# Robot_Psoc.net
KiCad netlist of a schematic drawn in EAGLE
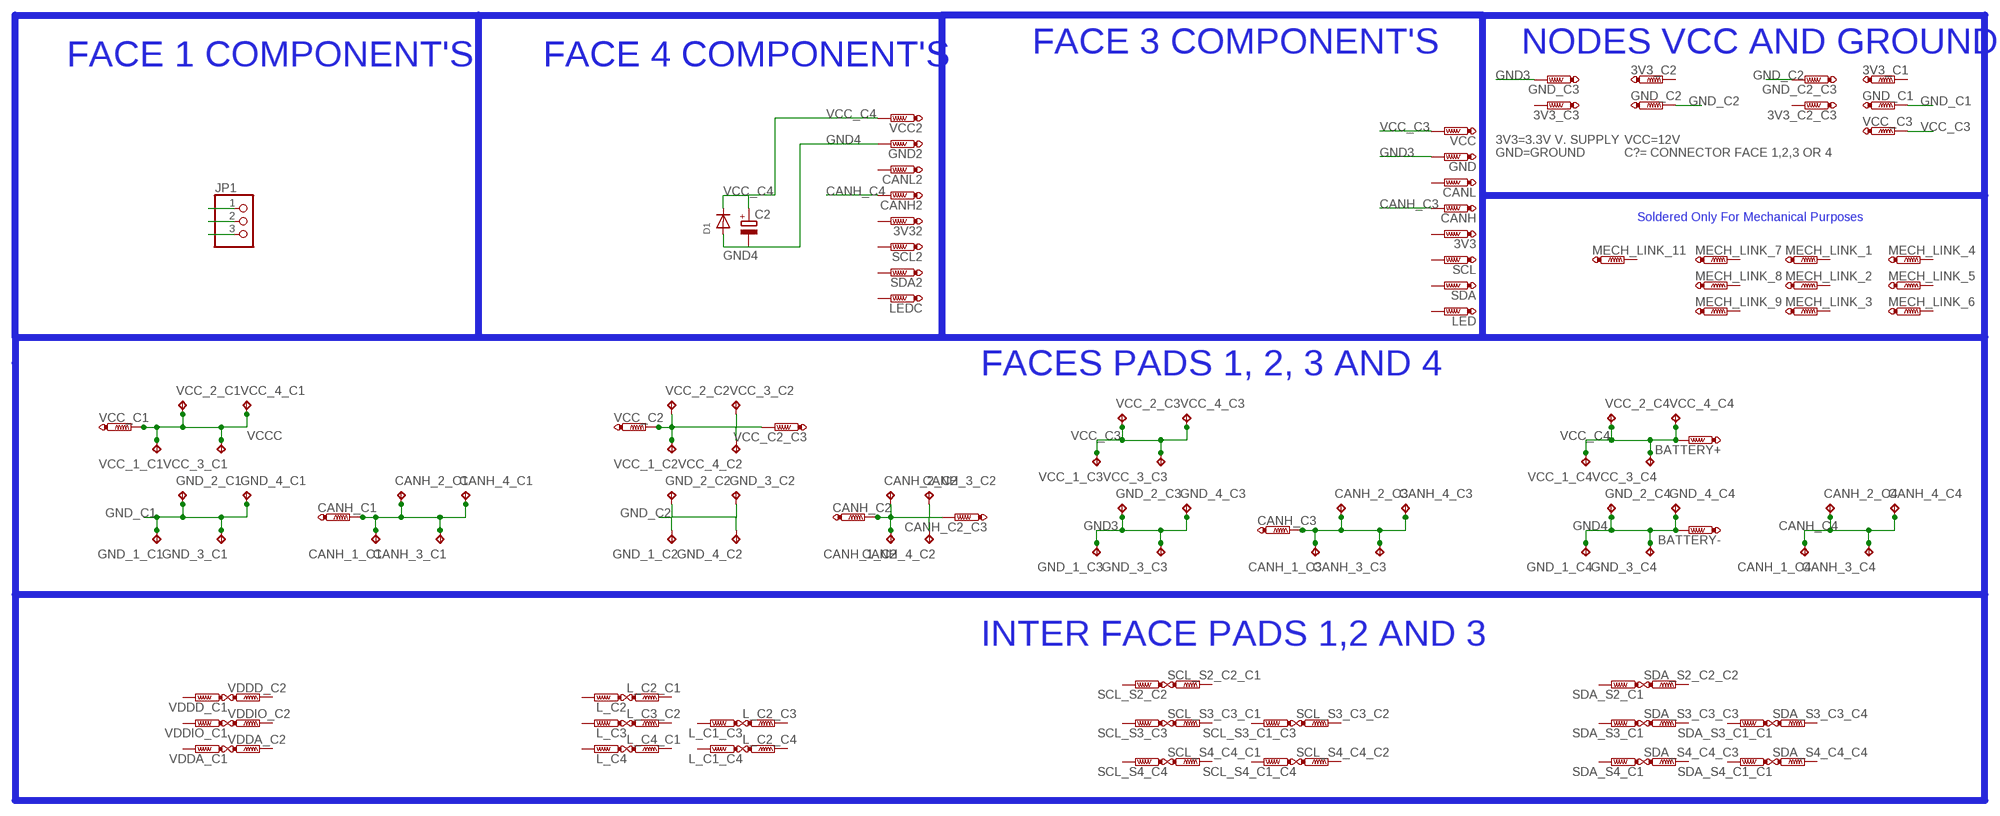
[diagram p0: schematic, sheet 1]

(export (version "E")
  (design (tool "Eeschema 10.0.6"))
  (components
    (comp (ref "3V3")
      (value "PTR1TP11R")
      (footprint "eagle-import:TP11R")
      (libsource (lib "eagle-import") (part "PTR1TP11R"))
    )
    (comp (ref "3V3_C1")
      (value "PTR1TP11R")
      (footprint "eagle-import:TP11R")
      (libsource (lib "eagle-import") (part "PTR1TP11R"))
    )
    (comp (ref "3V3_C2")
      (value "PTR1TP11R")
      (footprint "eagle-import:TP11R")
      (libsource (lib "eagle-import") (part "PTR1TP11R"))
    )
    (comp (ref "3V3_C2_C3")
      (value "PTR1TP11R")
      (footprint "eagle-import:TP11R")
      (libsource (lib "eagle-import") (part "PTR1TP11R"))
    )
    (comp (ref "3V3_C3")
      (value "PTR1TP11R")
      (footprint "eagle-import:TP11R")
      (libsource (lib "eagle-import") (part "PTR1TP11R"))
    )
    (comp (ref "3V32")
      (value "PTR1TP11R")
      (footprint "eagle-import:TP11R")
      (libsource (lib "eagle-import") (part "PTR1TP11R"))
    )
    (comp (ref "BATTERY+")
      (value "PTR1TP11R")
      (footprint "eagle-import:TP11R")
      (libsource (lib "eagle-import") (part "PTR1TP11R"))
    )
    (comp (ref "BATTERY-")
      (value "PTR1TP11R")
      (footprint "eagle-import:TP11R")
      (libsource (lib "eagle-import") (part "PTR1TP11R"))
    )
    (comp (ref "C2")
      (value "CPOL-EUUD-8X10")
      (footprint "eagle-import:UD-8X10_NICHICON")
      (libsource (lib "eagle-import") (part "CPOL-EUUD-8X10"))
    )
    (comp (ref "CANH")
      (value "PTR1TP11R")
      (footprint "eagle-import:TP11R")
      (libsource (lib "eagle-import") (part "PTR1TP11R"))
    )
    (comp (ref "CANH2")
      (value "PTR1TP11R")
      (footprint "eagle-import:TP11R")
      (libsource (lib "eagle-import") (part "PTR1TP11R"))
    )
    (comp (ref "CANH_1_C1")
      (value "TPB2,54")
      (footprint "eagle-import:B2,54")
      (libsource (lib "eagle-import") (part "TPB2,54"))
    )
    (comp (ref "CANH_1_C2")
      (value "TPB2,54")
      (footprint "eagle-import:B2,54")
      (libsource (lib "eagle-import") (part "TPB2,54"))
    )
    (comp (ref "CANH_1_C3")
      (value "TPB2,54")
      (footprint "eagle-import:B2,54")
      (libsource (lib "eagle-import") (part "TPB2,54"))
    )
    (comp (ref "CANH_1_C4")
      (value "TPB2,54")
      (footprint "eagle-import:B2,54")
      (libsource (lib "eagle-import") (part "TPB2,54"))
    )
    (comp (ref "CANH_2_C1")
      (value "TPB2,54")
      (footprint "eagle-import:B2,54")
      (libsource (lib "eagle-import") (part "TPB2,54"))
    )
    (comp (ref "CANH_2_C2")
      (value "TPB2,54")
      (footprint "eagle-import:B2,54")
      (libsource (lib "eagle-import") (part "TPB2,54"))
    )
    (comp (ref "CANH_2_C3")
      (value "TPB2,54")
      (footprint "eagle-import:B2,54")
      (libsource (lib "eagle-import") (part "TPB2,54"))
    )
    (comp (ref "CANH_2_C4")
      (value "TPB2,54")
      (footprint "eagle-import:B2,54")
      (libsource (lib "eagle-import") (part "TPB2,54"))
    )
    (comp (ref "CANH_3_C1")
      (value "TPB2,54")
      (footprint "eagle-import:B2,54")
      (libsource (lib "eagle-import") (part "TPB2,54"))
    )
    (comp (ref "CANH_3_C2")
      (value "TPB2,54")
      (footprint "eagle-import:B2,54")
      (libsource (lib "eagle-import") (part "TPB2,54"))
    )
    (comp (ref "CANH_3_C3")
      (value "TPB2,54")
      (footprint "eagle-import:B2,54")
      (libsource (lib "eagle-import") (part "TPB2,54"))
    )
    (comp (ref "CANH_3_C4")
      (value "TPB2,54")
      (footprint "eagle-import:B2,54")
      (libsource (lib "eagle-import") (part "TPB2,54"))
    )
    (comp (ref "CANH_4_C1")
      (value "TPB2,54")
      (footprint "eagle-import:B2,54")
      (libsource (lib "eagle-import") (part "TPB2,54"))
    )
    (comp (ref "CANH_4_C2")
      (value "TPB2,54")
      (footprint "eagle-import:B2,54")
      (libsource (lib "eagle-import") (part "TPB2,54"))
    )
    (comp (ref "CANH_4_C3")
      (value "TPB2,54")
      (footprint "eagle-import:B2,54")
      (libsource (lib "eagle-import") (part "TPB2,54"))
    )
    (comp (ref "CANH_4_C4")
      (value "TPB2,54")
      (footprint "eagle-import:B2,54")
      (libsource (lib "eagle-import") (part "TPB2,54"))
    )
    (comp (ref "CANH_C1")
      (value "PTR1TP11R")
      (footprint "eagle-import:TP11R")
      (libsource (lib "eagle-import") (part "PTR1TP11R"))
    )
    (comp (ref "CANH_C2")
      (value "PTR1TP11R")
      (footprint "eagle-import:TP11R")
      (libsource (lib "eagle-import") (part "PTR1TP11R"))
    )
    (comp (ref "CANH_C2_C3")
      (value "PTR1TP11R")
      (footprint "eagle-import:TP11R")
      (libsource (lib "eagle-import") (part "PTR1TP11R"))
    )
    (comp (ref "CANH_C3")
      (value "PTR1TP11R")
      (footprint "eagle-import:TP11R")
      (libsource (lib "eagle-import") (part "PTR1TP11R"))
    )
    (comp (ref "CANL")
      (value "PTR1TP11R")
      (footprint "eagle-import:TP11R")
      (libsource (lib "eagle-import") (part "PTR1TP11R"))
    )
    (comp (ref "CANL2")
      (value "PTR1TP11R")
      (footprint "eagle-import:TP11R")
      (libsource (lib "eagle-import") (part "PTR1TP11R"))
    )
    (comp (ref "D1")
      (value "DIODESMA")
      (footprint "eagle-import:SMADIODE")
      (libsource (lib "eagle-import") (part "DIODESMA"))
    )
    (comp (ref "GND")
      (value "PTR1TP11R")
      (footprint "eagle-import:TP11R")
      (libsource (lib "eagle-import") (part "PTR1TP11R"))
    )
    (comp (ref "GND2")
      (value "PTR1TP11R")
      (footprint "eagle-import:TP11R")
      (libsource (lib "eagle-import") (part "PTR1TP11R"))
    )
    (comp (ref "GND_1_C1")
      (value "TPB2,54")
      (footprint "eagle-import:B2,54")
      (libsource (lib "eagle-import") (part "TPB2,54"))
    )
    (comp (ref "GND_1_C2")
      (value "TPB2,54")
      (footprint "eagle-import:B2,54")
      (libsource (lib "eagle-import") (part "TPB2,54"))
    )
    (comp (ref "GND_1_C3")
      (value "TPB2,54")
      (footprint "eagle-import:B2,54")
      (libsource (lib "eagle-import") (part "TPB2,54"))
    )
    (comp (ref "GND_1_C4")
      (value "TPB2,54")
      (footprint "eagle-import:B2,54")
      (libsource (lib "eagle-import") (part "TPB2,54"))
    )
    (comp (ref "GND_2_C1")
      (value "TPB2,54")
      (footprint "eagle-import:B2,54")
      (libsource (lib "eagle-import") (part "TPB2,54"))
    )
    (comp (ref "GND_2_C2")
      (value "TPB2,54")
      (footprint "eagle-import:B2,54")
      (libsource (lib "eagle-import") (part "TPB2,54"))
    )
    (comp (ref "GND_2_C3")
      (value "TPB2,54")
      (footprint "eagle-import:B2,54")
      (libsource (lib "eagle-import") (part "TPB2,54"))
    )
    (comp (ref "GND_2_C4")
      (value "TPB2,54")
      (footprint "eagle-import:B2,54")
      (libsource (lib "eagle-import") (part "TPB2,54"))
    )
    (comp (ref "GND_3_C1")
      (value "TPB2,54")
      (footprint "eagle-import:B2,54")
      (libsource (lib "eagle-import") (part "TPB2,54"))
    )
    (comp (ref "GND_3_C2")
      (value "TPB2,54")
      (footprint "eagle-import:B2,54")
      (libsource (lib "eagle-import") (part "TPB2,54"))
    )
    (comp (ref "GND_3_C3")
      (value "TPB2,54")
      (footprint "eagle-import:B2,54")
      (libsource (lib "eagle-import") (part "TPB2,54"))
    )
    (comp (ref "GND_3_C4")
      (value "TPB2,54")
      (footprint "eagle-import:B2,54")
      (libsource (lib "eagle-import") (part "TPB2,54"))
    )
    (comp (ref "GND_4_C1")
      (value "TPB2,54")
      (footprint "eagle-import:B2,54")
      (libsource (lib "eagle-import") (part "TPB2,54"))
    )
    (comp (ref "GND_4_C2")
      (value "TPB2,54")
      (footprint "eagle-import:B2,54")
      (libsource (lib "eagle-import") (part "TPB2,54"))
    )
    (comp (ref "GND_4_C3")
      (value "TPB2,54")
      (footprint "eagle-import:B2,54")
      (libsource (lib "eagle-import") (part "TPB2,54"))
    )
    (comp (ref "GND_4_C4")
      (value "TPB2,54")
      (footprint "eagle-import:B2,54")
      (libsource (lib "eagle-import") (part "TPB2,54"))
    )
    (comp (ref "GND_C1")
      (value "PTR1TP11R")
      (footprint "eagle-import:TP11R")
      (libsource (lib "eagle-import") (part "PTR1TP11R"))
    )
    (comp (ref "GND_C2")
      (value "PTR1TP11R")
      (footprint "eagle-import:TP11R")
      (libsource (lib "eagle-import") (part "PTR1TP11R"))
    )
    (comp (ref "GND_C2_C3")
      (value "PTR1TP11R")
      (footprint "eagle-import:TP11R")
      (libsource (lib "eagle-import") (part "PTR1TP11R"))
    )
    (comp (ref "GND_C3")
      (value "PTR1TP11R")
      (footprint "eagle-import:TP11R")
      (libsource (lib "eagle-import") (part "PTR1TP11R"))
    )
    (comp (ref "JP1")
      (value "PINHD-1X3")
      (footprint "eagle-import:1X03")
      (libsource (lib "eagle-import") (part "PINHD-1X3"))
    )
    (comp (ref "LED")
      (value "PTR1TP11R")
      (footprint "eagle-import:TP11R")
      (libsource (lib "eagle-import") (part "PTR1TP11R"))
    )
    (comp (ref "LEDC")
      (value "PTR1TP11R")
      (footprint "eagle-import:TP11R")
      (libsource (lib "eagle-import") (part "PTR1TP11R"))
    )
    (comp (ref "L_C1_C3")
      (value "PTR1TP11R")
      (footprint "eagle-import:TP11R")
      (libsource (lib "eagle-import") (part "PTR1TP11R"))
    )
    (comp (ref "L_C1_C4")
      (value "PTR1TP11R")
      (footprint "eagle-import:TP11R")
      (libsource (lib "eagle-import") (part "PTR1TP11R"))
    )
    (comp (ref "L_C2")
      (value "PTR1TP11R")
      (footprint "eagle-import:TP11R")
      (libsource (lib "eagle-import") (part "PTR1TP11R"))
    )
    (comp (ref "L_C2_C1")
      (value "PTR1TP11R")
      (footprint "eagle-import:TP11R")
      (libsource (lib "eagle-import") (part "PTR1TP11R"))
    )
    (comp (ref "L_C2_C3")
      (value "PTR1TP11R")
      (footprint "eagle-import:TP11R")
      (libsource (lib "eagle-import") (part "PTR1TP11R"))
    )
    (comp (ref "L_C2_C4")
      (value "PTR1TP11R")
      (footprint "eagle-import:TP11R")
      (libsource (lib "eagle-import") (part "PTR1TP11R"))
    )
    (comp (ref "L_C3")
      (value "PTR1TP11R")
      (footprint "eagle-import:TP11R")
      (libsource (lib "eagle-import") (part "PTR1TP11R"))
    )
    (comp (ref "L_C3_C2")
      (value "PTR1TP11R")
      (footprint "eagle-import:TP11R")
      (libsource (lib "eagle-import") (part "PTR1TP11R"))
    )
    (comp (ref "L_C4")
      (value "PTR1TP11R")
      (footprint "eagle-import:TP11R")
      (libsource (lib "eagle-import") (part "PTR1TP11R"))
    )
    (comp (ref "L_C4_C1")
      (value "PTR1TP11R")
      (footprint "eagle-import:TP11R")
      (libsource (lib "eagle-import") (part "PTR1TP11R"))
    )
    (comp (ref "MECH_LINK_1")
      (value "PTR1TP11R")
      (footprint "eagle-import:TP11R")
      (libsource (lib "eagle-import") (part "PTR1TP11R"))
    )
    (comp (ref "MECH_LINK_2")
      (value "PTR1TP11R")
      (footprint "eagle-import:TP11R")
      (libsource (lib "eagle-import") (part "PTR1TP11R"))
    )
    (comp (ref "MECH_LINK_3")
      (value "PTR1TP11R")
      (footprint "eagle-import:TP11R")
      (libsource (lib "eagle-import") (part "PTR1TP11R"))
    )
    (comp (ref "MECH_LINK_4")
      (value "PTR1TP11R")
      (footprint "eagle-import:TP11R")
      (libsource (lib "eagle-import") (part "PTR1TP11R"))
    )
    (comp (ref "MECH_LINK_5")
      (value "PTR1TP11R")
      (footprint "eagle-import:TP11R")
      (libsource (lib "eagle-import") (part "PTR1TP11R"))
    )
    (comp (ref "MECH_LINK_6")
      (value "PTR1TP11R")
      (footprint "eagle-import:TP11R")
      (libsource (lib "eagle-import") (part "PTR1TP11R"))
    )
    (comp (ref "MECH_LINK_7")
      (value "PTR1TP11R")
      (footprint "eagle-import:TP11R")
      (libsource (lib "eagle-import") (part "PTR1TP11R"))
    )
    (comp (ref "MECH_LINK_8")
      (value "PTR1TP11R")
      (footprint "eagle-import:TP11R")
      (libsource (lib "eagle-import") (part "PTR1TP11R"))
    )
    (comp (ref "MECH_LINK_9")
      (value "PTR1TP11R")
      (footprint "eagle-import:TP11R")
      (libsource (lib "eagle-import") (part "PTR1TP11R"))
    )
    (comp (ref "MECH_LINK_11")
      (value "PTR1TP11R")
      (footprint "eagle-import:TP11R")
      (libsource (lib "eagle-import") (part "PTR1TP11R"))
    )
    (comp (ref "SCL")
      (value "PTR1TP11R")
      (footprint "eagle-import:TP11R")
      (libsource (lib "eagle-import") (part "PTR1TP11R"))
    )
    (comp (ref "SCL2")
      (value "PTR1TP11R")
      (footprint "eagle-import:TP11R")
      (libsource (lib "eagle-import") (part "PTR1TP11R"))
    )
    (comp (ref "SCL_S2_C2")
      (value "PTR1TP11R")
      (footprint "eagle-import:TP11R")
      (libsource (lib "eagle-import") (part "PTR1TP11R"))
    )
    (comp (ref "SCL_S2_C2_C1")
      (value "PTR1TP11R")
      (footprint "eagle-import:TP11R")
      (libsource (lib "eagle-import") (part "PTR1TP11R"))
    )
    (comp (ref "SCL_S3_C1_C3")
      (value "PTR1TP11R")
      (footprint "eagle-import:TP11R")
      (libsource (lib "eagle-import") (part "PTR1TP11R"))
    )
    (comp (ref "SCL_S3_C3")
      (value "PTR1TP11R")
      (footprint "eagle-import:TP11R")
      (libsource (lib "eagle-import") (part "PTR1TP11R"))
    )
    (comp (ref "SCL_S3_C3_C1")
      (value "PTR1TP11R")
      (footprint "eagle-import:TP11R")
      (libsource (lib "eagle-import") (part "PTR1TP11R"))
    )
    (comp (ref "SCL_S3_C3_C2")
      (value "PTR1TP11R")
      (footprint "eagle-import:TP11R")
      (libsource (lib "eagle-import") (part "PTR1TP11R"))
    )
    (comp (ref "SCL_S4_C1_C4")
      (value "PTR1TP11R")
      (footprint "eagle-import:TP11R")
      (libsource (lib "eagle-import") (part "PTR1TP11R"))
    )
    (comp (ref "SCL_S4_C4")
      (value "PTR1TP11R")
      (footprint "eagle-import:TP11R")
      (libsource (lib "eagle-import") (part "PTR1TP11R"))
    )
    (comp (ref "SCL_S4_C4_C1")
      (value "PTR1TP11R")
      (footprint "eagle-import:TP11R")
      (libsource (lib "eagle-import") (part "PTR1TP11R"))
    )
    (comp (ref "SCL_S4_C4_C2")
      (value "PTR1TP11R")
      (footprint "eagle-import:TP11R")
      (libsource (lib "eagle-import") (part "PTR1TP11R"))
    )
    (comp (ref "SDA")
      (value "PTR1TP11R")
      (footprint "eagle-import:TP11R")
      (libsource (lib "eagle-import") (part "PTR1TP11R"))
    )
    (comp (ref "SDA2")
      (value "PTR1TP11R")
      (footprint "eagle-import:TP11R")
      (libsource (lib "eagle-import") (part "PTR1TP11R"))
    )
    (comp (ref "SDA_S2_C1")
      (value "PTR1TP11R")
      (footprint "eagle-import:TP11R")
      (libsource (lib "eagle-import") (part "PTR1TP11R"))
    )
    (comp (ref "SDA_S2_C2_C2")
      (value "PTR1TP11R")
      (footprint "eagle-import:TP11R")
      (libsource (lib "eagle-import") (part "PTR1TP11R"))
    )
    (comp (ref "SDA_S3_C1")
      (value "PTR1TP11R")
      (footprint "eagle-import:TP11R")
      (libsource (lib "eagle-import") (part "PTR1TP11R"))
    )
    (comp (ref "SDA_S3_C1_C1")
      (value "PTR1TP11R")
      (footprint "eagle-import:TP11R")
      (libsource (lib "eagle-import") (part "PTR1TP11R"))
    )
    (comp (ref "SDA_S3_C3_C3")
      (value "PTR1TP11R")
      (footprint "eagle-import:TP11R")
      (libsource (lib "eagle-import") (part "PTR1TP11R"))
    )
    (comp (ref "SDA_S3_C3_C4")
      (value "PTR1TP11R")
      (footprint "eagle-import:TP11R")
      (libsource (lib "eagle-import") (part "PTR1TP11R"))
    )
    (comp (ref "SDA_S4_C1")
      (value "PTR1TP11R")
      (footprint "eagle-import:TP11R")
      (libsource (lib "eagle-import") (part "PTR1TP11R"))
    )
    (comp (ref "SDA_S4_C1_C1")
      (value "PTR1TP11R")
      (footprint "eagle-import:TP11R")
      (libsource (lib "eagle-import") (part "PTR1TP11R"))
    )
    (comp (ref "SDA_S4_C4_C3")
      (value "PTR1TP11R")
      (footprint "eagle-import:TP11R")
      (libsource (lib "eagle-import") (part "PTR1TP11R"))
    )
    (comp (ref "SDA_S4_C4_C4")
      (value "PTR1TP11R")
      (footprint "eagle-import:TP11R")
      (libsource (lib "eagle-import") (part "PTR1TP11R"))
    )
    (comp (ref "VCC")
      (value "PTR1TP11R")
      (footprint "eagle-import:TP11R")
      (libsource (lib "eagle-import") (part "PTR1TP11R"))
    )
    (comp (ref "VCC2")
      (value "PTR1TP11R")
      (footprint "eagle-import:TP11R")
      (libsource (lib "eagle-import") (part "PTR1TP11R"))
    )
    (comp (ref "VCC_1_C1")
      (value "TPB2,54")
      (footprint "eagle-import:B2,54")
      (libsource (lib "eagle-import") (part "TPB2,54"))
    )
    (comp (ref "VCC_1_C2")
      (value "TPB2,54")
      (footprint "eagle-import:B2,54")
      (libsource (lib "eagle-import") (part "TPB2,54"))
    )
    (comp (ref "VCC_1_C3")
      (value "TPB2,54")
      (footprint "eagle-import:B2,54")
      (libsource (lib "eagle-import") (part "TPB2,54"))
    )
    (comp (ref "VCC_1_C4")
      (value "TPB2,54")
      (footprint "eagle-import:B2,54")
      (libsource (lib "eagle-import") (part "TPB2,54"))
    )
    (comp (ref "VCC_2_C1")
      (value "TPB2,54")
      (footprint "eagle-import:B2,54")
      (libsource (lib "eagle-import") (part "TPB2,54"))
    )
    (comp (ref "VCC_2_C2")
      (value "TPB2,54")
      (footprint "eagle-import:B2,54")
      (libsource (lib "eagle-import") (part "TPB2,54"))
    )
    (comp (ref "VCC_2_C3")
      (value "TPB2,54")
      (footprint "eagle-import:B2,54")
      (libsource (lib "eagle-import") (part "TPB2,54"))
    )
    (comp (ref "VCC_2_C4")
      (value "TPB2,54")
      (footprint "eagle-import:B2,54")
      (libsource (lib "eagle-import") (part "TPB2,54"))
    )
    (comp (ref "VCC_3_C1")
      (value "TPB2,54")
      (footprint "eagle-import:B2,54")
      (libsource (lib "eagle-import") (part "TPB2,54"))
    )
    (comp (ref "VCC_3_C2")
      (value "TPB2,54")
      (footprint "eagle-import:B2,54")
      (libsource (lib "eagle-import") (part "TPB2,54"))
    )
    (comp (ref "VCC_3_C3")
      (value "TPB2,54")
      (footprint "eagle-import:B2,54")
      (libsource (lib "eagle-import") (part "TPB2,54"))
    )
    (comp (ref "VCC_3_C4")
      (value "TPB2,54")
      (footprint "eagle-import:B2,54")
      (libsource (lib "eagle-import") (part "TPB2,54"))
    )
    (comp (ref "VCC_4_C1")
      (value "TPB2,54")
      (footprint "eagle-import:B2,54")
      (libsource (lib "eagle-import") (part "TPB2,54"))
    )
    (comp (ref "VCC_4_C2")
      (value "TPB2,54")
      (footprint "eagle-import:B2,54")
      (libsource (lib "eagle-import") (part "TPB2,54"))
    )
    (comp (ref "VCC_4_C3")
      (value "TPB2,54")
      (footprint "eagle-import:B2,54")
      (libsource (lib "eagle-import") (part "TPB2,54"))
    )
    (comp (ref "VCC_4_C4")
      (value "TPB2,54")
      (footprint "eagle-import:B2,54")
      (libsource (lib "eagle-import") (part "TPB2,54"))
    )
    (comp (ref "VCC_C1")
      (value "PTR1TP11R")
      (footprint "eagle-import:TP11R")
      (libsource (lib "eagle-import") (part "PTR1TP11R"))
    )
    (comp (ref "VCC_C2")
      (value "PTR1TP11R")
      (footprint "eagle-import:TP11R")
      (libsource (lib "eagle-import") (part "PTR1TP11R"))
    )
    (comp (ref "VCC_C2_C3")
      (value "PTR1TP11R")
      (footprint "eagle-import:TP11R")
      (libsource (lib "eagle-import") (part "PTR1TP11R"))
    )
    (comp (ref "VCC_C3")
      (value "PTR1TP11R")
      (footprint "eagle-import:TP11R")
      (libsource (lib "eagle-import") (part "PTR1TP11R"))
    )
    (comp (ref "VDDA_C1")
      (value "PTR1TP11R")
      (footprint "eagle-import:TP11R")
      (libsource (lib "eagle-import") (part "PTR1TP11R"))
    )
    (comp (ref "VDDA_C2")
      (value "PTR1TP11R")
      (footprint "eagle-import:TP11R")
      (libsource (lib "eagle-import") (part "PTR1TP11R"))
    )
    (comp (ref "VDDD_C1")
      (value "PTR1TP11R")
      (footprint "eagle-import:TP11R")
      (libsource (lib "eagle-import") (part "PTR1TP11R"))
    )
    (comp (ref "VDDD_C2")
      (value "PTR1TP11R")
      (footprint "eagle-import:TP11R")
      (libsource (lib "eagle-import") (part "PTR1TP11R"))
    )
    (comp (ref "VDDIO_C1")
      (value "PTR1TP11R")
      (footprint "eagle-import:TP11R")
      (libsource (lib "eagle-import") (part "PTR1TP11R"))
    )
    (comp (ref "VDDIO_C2")
      (value "PTR1TP11R")
      (footprint "eagle-import:TP11R")
      (libsource (lib "eagle-import") (part "PTR1TP11R"))
    )
  )
  (nets
    (net (code "1") (name "/CANH") (class "Default")
      (node (ref "CANH_1_C1") (pin "TP") (pinfunction "TP_TP") (pintype "input"))
      (node (ref "CANH_2_C1") (pin "TP") (pinfunction "TP_TP") (pintype "input"))
      (node (ref "CANH_3_C1") (pin "TP") (pinfunction "TP_TP") (pintype "input"))
      (node (ref "CANH_4_C1") (pin "TP") (pinfunction "TP_TP") (pintype "input"))
      (node (ref "CANH_C1") (pin "TP") (pinfunction "TP_TP") (pintype "input"))
      (node (ref "JP1") (pin "3") (pinfunction "3_3") (pintype "passive"))
    )
    (net (code "2") (name "/CANH_C3") (class "Default")
      (node (ref "CANH") (pin "TP") (pinfunction "TP_TP") (pintype "input"))
      (node (ref "CANH_1_C3") (pin "TP") (pinfunction "TP_TP") (pintype "input"))
      (node (ref "CANH_2_C3") (pin "TP") (pinfunction "TP_TP") (pintype "input"))
      (node (ref "CANH_3_C3") (pin "TP") (pinfunction "TP_TP") (pintype "input"))
      (node (ref "CANH_4_C3") (pin "TP") (pinfunction "TP_TP") (pintype "input"))
      (node (ref "CANH_C3") (pin "TP") (pinfunction "TP_TP") (pintype "input"))
    )
    (net (code "3") (name "/CANH_C4") (class "Default")
      (node (ref "CANH2") (pin "TP") (pinfunction "TP_TP") (pintype "input"))
      (node (ref "CANH_1_C4") (pin "TP") (pinfunction "TP_TP") (pintype "input"))
      (node (ref "CANH_2_C4") (pin "TP") (pinfunction "TP_TP") (pintype "input"))
      (node (ref "CANH_3_C4") (pin "TP") (pinfunction "TP_TP") (pintype "input"))
      (node (ref "CANH_4_C4") (pin "TP") (pinfunction "TP_TP") (pintype "input"))
    )
    (net (code "4") (name "/GND3") (class "Default")
      (node (ref "GND") (pin "TP") (pinfunction "TP_TP") (pintype "input"))
      (node (ref "GND_1_C3") (pin "TP") (pinfunction "TP_TP") (pintype "input"))
      (node (ref "GND_2_C3") (pin "TP") (pinfunction "TP_TP") (pintype "input"))
      (node (ref "GND_3_C3") (pin "TP") (pinfunction "TP_TP") (pintype "input"))
      (node (ref "GND_4_C3") (pin "TP") (pinfunction "TP_TP") (pintype "input"))
      (node (ref "GND_C3") (pin "TP") (pinfunction "TP_TP") (pintype "input"))
    )
    (net (code "5") (name "/GND4") (class "Default")
      (node (ref "BATTERY-") (pin "TP") (pinfunction "TP_TP") (pintype "input"))
      (node (ref "C2") (pin "-") (pinfunction "-_-") (pintype "passive"))
      (node (ref "D1") (pin "A") (pinfunction "A_A") (pintype "passive"))
      (node (ref "GND2") (pin "TP") (pinfunction "TP_TP") (pintype "input"))
      (node (ref "GND_1_C4") (pin "TP") (pinfunction "TP_TP") (pintype "input"))
      (node (ref "GND_2_C4") (pin "TP") (pinfunction "TP_TP") (pintype "input"))
      (node (ref "GND_3_C4") (pin "TP") (pinfunction "TP_TP") (pintype "input"))
      (node (ref "GND_4_C4") (pin "TP") (pinfunction "TP_TP") (pintype "input"))
    )
    (net (code "6") (name "/GND_C1") (class "Default")
      (node (ref "GND_1_C1") (pin "TP") (pinfunction "TP_TP") (pintype "input"))
      (node (ref "GND_2_C1") (pin "TP") (pinfunction "TP_TP") (pintype "input"))
      (node (ref "GND_3_C1") (pin "TP") (pinfunction "TP_TP") (pintype "input"))
      (node (ref "GND_4_C1") (pin "TP") (pinfunction "TP_TP") (pintype "input"))
      (node (ref "GND_C1") (pin "TP") (pinfunction "TP_TP") (pintype "input"))
      (node (ref "JP1") (pin "2") (pinfunction "2_2") (pintype "passive"))
    )
    (net (code "7") (name "/GND_C2") (class "Default")
      (node (ref "GND_1_C2") (pin "TP") (pinfunction "TP_TP") (pintype "input"))
      (node (ref "GND_2_C2") (pin "TP") (pinfunction "TP_TP") (pintype "input"))
      (node (ref "GND_3_C2") (pin "TP") (pinfunction "TP_TP") (pintype "input"))
      (node (ref "GND_4_C2") (pin "TP") (pinfunction "TP_TP") (pintype "input"))
      (node (ref "GND_C2") (pin "TP") (pinfunction "TP_TP") (pintype "input"))
      (node (ref "GND_C2_C3") (pin "TP") (pinfunction "TP_TP") (pintype "input"))
    )
    (net (code "8") (name "/VCCC") (class "Default")
      (node (ref "JP1") (pin "1") (pinfunction "1_1") (pintype "passive"))
      (node (ref "VCC_1_C1") (pin "TP") (pinfunction "TP_TP") (pintype "input"))
      (node (ref "VCC_2_C1") (pin "TP") (pinfunction "TP_TP") (pintype "input"))
      (node (ref "VCC_3_C1") (pin "TP") (pinfunction "TP_TP") (pintype "input"))
      (node (ref "VCC_4_C1") (pin "TP") (pinfunction "TP_TP") (pintype "input"))
      (node (ref "VCC_C1") (pin "TP") (pinfunction "TP_TP") (pintype "input"))
    )
    (net (code "9") (name "/VCC_C3") (class "Default")
      (node (ref "VCC") (pin "TP") (pinfunction "TP_TP") (pintype "input"))
      (node (ref "VCC_1_C3") (pin "TP") (pinfunction "TP_TP") (pintype "input"))
      (node (ref "VCC_2_C3") (pin "TP") (pinfunction "TP_TP") (pintype "input"))
      (node (ref "VCC_3_C3") (pin "TP") (pinfunction "TP_TP") (pintype "input"))
      (node (ref "VCC_4_C3") (pin "TP") (pinfunction "TP_TP") (pintype "input"))
      (node (ref "VCC_C3") (pin "TP") (pinfunction "TP_TP") (pintype "input"))
    )
    (net (code "10") (name "/VCC_C4") (class "Default")
      (node (ref "BATTERY+") (pin "TP") (pinfunction "TP_TP") (pintype "input"))
      (node (ref "C2") (pin "+") (pinfunction "+_+") (pintype "passive"))
      (node (ref "D1") (pin "C") (pinfunction "C_C") (pintype "passive"))
      (node (ref "VCC2") (pin "TP") (pinfunction "TP_TP") (pintype "input"))
      (node (ref "VCC_1_C4") (pin "TP") (pinfunction "TP_TP") (pintype "input"))
      (node (ref "VCC_2_C4") (pin "TP") (pinfunction "TP_TP") (pintype "input"))
      (node (ref "VCC_3_C4") (pin "TP") (pinfunction "TP_TP") (pintype "input"))
      (node (ref "VCC_4_C4") (pin "TP") (pinfunction "TP_TP") (pintype "input"))
    )
    (net (code "11") (name "Net-(CANH_1_C2-PadTP)") (class "Default")
      (node (ref "CANH_1_C2") (pin "TP") (pinfunction "TP_TP") (pintype "input"))
      (node (ref "CANH_2_C2") (pin "TP") (pinfunction "TP_TP") (pintype "input"))
      (node (ref "CANH_3_C2") (pin "TP") (pinfunction "TP_TP") (pintype "input"))
      (node (ref "CANH_4_C2") (pin "TP") (pinfunction "TP_TP") (pintype "input"))
      (node (ref "CANH_C2") (pin "TP") (pinfunction "TP_TP") (pintype "input"))
      (node (ref "CANH_C2_C3") (pin "TP") (pinfunction "TP_TP") (pintype "input"))
    )
    (net (code "12") (name "Net-(VCC_1_C2-PadTP)") (class "Default")
      (node (ref "VCC_1_C2") (pin "TP") (pinfunction "TP_TP") (pintype "input"))
      (node (ref "VCC_2_C2") (pin "TP") (pinfunction "TP_TP") (pintype "input"))
      (node (ref "VCC_3_C2") (pin "TP") (pinfunction "TP_TP") (pintype "input"))
      (node (ref "VCC_4_C2") (pin "TP") (pinfunction "TP_TP") (pintype "input"))
      (node (ref "VCC_C2") (pin "TP") (pinfunction "TP_TP") (pintype "input"))
      (node (ref "VCC_C2_C3") (pin "TP") (pinfunction "TP_TP") (pintype "input"))
    )
    (net (code "13") (name "unconnected-(3V3-PadTP)") (class "Default")
      (node (ref "3V3") (pin "TP") (pinfunction "TP_TP") (pintype "input"))
    )
    (net (code "14") (name "unconnected-(3V3_C1-PadTP)") (class "Default")
      (node (ref "3V3_C1") (pin "TP") (pinfunction "TP_TP") (pintype "input"))
    )
    (net (code "15") (name "unconnected-(3V3_C2-PadTP)") (class "Default")
      (node (ref "3V3_C2") (pin "TP") (pinfunction "TP_TP") (pintype "input"))
    )
    (net (code "16") (name "unconnected-(3V3_C2_C3-PadTP)") (class "Default")
      (node (ref "3V3_C2_C3") (pin "TP") (pinfunction "TP_TP") (pintype "input"))
    )
    (net (code "17") (name "unconnected-(3V3_C3-PadTP)") (class "Default")
      (node (ref "3V3_C3") (pin "TP") (pinfunction "TP_TP") (pintype "input"))
    )
    (net (code "18") (name "unconnected-(3V32-PadTP)") (class "Default")
      (node (ref "3V32") (pin "TP") (pinfunction "TP_TP") (pintype "input"))
    )
    (net (code "19") (name "unconnected-(CANL-PadTP)") (class "Default")
      (node (ref "CANL") (pin "TP") (pinfunction "TP_TP") (pintype "input"))
    )
    (net (code "20") (name "unconnected-(CANL2-PadTP)") (class "Default")
      (node (ref "CANL2") (pin "TP") (pinfunction "TP_TP") (pintype "input"))
    )
    (net (code "21") (name "unconnected-(LED-PadTP)") (class "Default")
      (node (ref "LED") (pin "TP") (pinfunction "TP_TP") (pintype "input"))
    )
    (net (code "22") (name "unconnected-(LEDC-PadTP)") (class "Default")
      (node (ref "LEDC") (pin "TP") (pinfunction "TP_TP") (pintype "input"))
    )
    (net (code "23") (name "unconnected-(L_C1_C3-PadTP)") (class "Default")
      (node (ref "L_C1_C3") (pin "TP") (pinfunction "TP_TP") (pintype "input"))
    )
    (net (code "24") (name "unconnected-(L_C1_C4-PadTP)") (class "Default")
      (node (ref "L_C1_C4") (pin "TP") (pinfunction "TP_TP") (pintype "input"))
    )
    (net (code "25") (name "unconnected-(L_C2-PadTP)") (class "Default")
      (node (ref "L_C2") (pin "TP") (pinfunction "TP_TP") (pintype "input"))
    )
    (net (code "26") (name "unconnected-(L_C2_C1-PadTP)") (class "Default")
      (node (ref "L_C2_C1") (pin "TP") (pinfunction "TP_TP") (pintype "input"))
    )
    (net (code "27") (name "unconnected-(L_C2_C3-PadTP)") (class "Default")
      (node (ref "L_C2_C3") (pin "TP") (pinfunction "TP_TP") (pintype "input"))
    )
    (net (code "28") (name "unconnected-(L_C2_C4-PadTP)") (class "Default")
      (node (ref "L_C2_C4") (pin "TP") (pinfunction "TP_TP") (pintype "input"))
    )
    (net (code "29") (name "unconnected-(L_C3-PadTP)") (class "Default")
      (node (ref "L_C3") (pin "TP") (pinfunction "TP_TP") (pintype "input"))
    )
    (net (code "30") (name "unconnected-(L_C3_C2-PadTP)") (class "Default")
      (node (ref "L_C3_C2") (pin "TP") (pinfunction "TP_TP") (pintype "input"))
    )
    (net (code "31") (name "unconnected-(L_C4-PadTP)") (class "Default")
      (node (ref "L_C4") (pin "TP") (pinfunction "TP_TP") (pintype "input"))
    )
    (net (code "32") (name "unconnected-(L_C4_C1-PadTP)") (class "Default")
      (node (ref "L_C4_C1") (pin "TP") (pinfunction "TP_TP") (pintype "input"))
    )
    (net (code "33") (name "unconnected-(MECH_LINK_1-PadTP)") (class "Default")
      (node (ref "MECH_LINK_1") (pin "TP") (pinfunction "TP_TP") (pintype "input"))
    )
    (net (code "34") (name "unconnected-(MECH_LINK_2-PadTP)") (class "Default")
      (node (ref "MECH_LINK_2") (pin "TP") (pinfunction "TP_TP") (pintype "input"))
    )
    (net (code "35") (name "unconnected-(MECH_LINK_3-PadTP)") (class "Default")
      (node (ref "MECH_LINK_3") (pin "TP") (pinfunction "TP_TP") (pintype "input"))
    )
    (net (code "36") (name "unconnected-(MECH_LINK_4-PadTP)") (class "Default")
      (node (ref "MECH_LINK_4") (pin "TP") (pinfunction "TP_TP") (pintype "input"))
    )
    (net (code "37") (name "unconnected-(MECH_LINK_5-PadTP)") (class "Default")
      (node (ref "MECH_LINK_5") (pin "TP") (pinfunction "TP_TP") (pintype "input"))
    )
    (net (code "38") (name "unconnected-(MECH_LINK_6-PadTP)") (class "Default")
      (node (ref "MECH_LINK_6") (pin "TP") (pinfunction "TP_TP") (pintype "input"))
    )
    (net (code "39") (name "unconnected-(MECH_LINK_7-PadTP)") (class "Default")
      (node (ref "MECH_LINK_7") (pin "TP") (pinfunction "TP_TP") (pintype "input"))
    )
    (net (code "40") (name "unconnected-(MECH_LINK_8-PadTP)") (class "Default")
      (node (ref "MECH_LINK_8") (pin "TP") (pinfunction "TP_TP") (pintype "input"))
    )
    (net (code "41") (name "unconnected-(MECH_LINK_9-PadTP)") (class "Default")
      (node (ref "MECH_LINK_9") (pin "TP") (pinfunction "TP_TP") (pintype "input"))
    )
    (net (code "42") (name "unconnected-(MECH_LINK_11-PadTP)") (class "Default")
      (node (ref "MECH_LINK_11") (pin "TP") (pinfunction "TP_TP") (pintype "input"))
    )
    (net (code "43") (name "unconnected-(SCL-PadTP)") (class "Default")
      (node (ref "SCL") (pin "TP") (pinfunction "TP_TP") (pintype "input"))
    )
    (net (code "44") (name "unconnected-(SCL2-PadTP)") (class "Default")
      (node (ref "SCL2") (pin "TP") (pinfunction "TP_TP") (pintype "input"))
    )
    (net (code "45") (name "unconnected-(SCL_S2_C2-PadTP)") (class "Default")
      (node (ref "SCL_S2_C2") (pin "TP") (pinfunction "TP_TP") (pintype "input"))
    )
    (net (code "46") (name "unconnected-(SCL_S2_C2_C1-PadTP)") (class "Default")
      (node (ref "SCL_S2_C2_C1") (pin "TP") (pinfunction "TP_TP") (pintype "input"))
    )
    (net (code "47") (name "unconnected-(SCL_S3_C1_C3-PadTP)") (class "Default")
      (node (ref "SCL_S3_C1_C3") (pin "TP") (pinfunction "TP_TP") (pintype "input"))
    )
    (net (code "48") (name "unconnected-(SCL_S3_C3-PadTP)") (class "Default")
      (node (ref "SCL_S3_C3") (pin "TP") (pinfunction "TP_TP") (pintype "input"))
    )
    (net (code "49") (name "unconnected-(SCL_S3_C3_C1-PadTP)") (class "Default")
      (node (ref "SCL_S3_C3_C1") (pin "TP") (pinfunction "TP_TP") (pintype "input"))
    )
    (net (code "50") (name "unconnected-(SCL_S3_C3_C2-PadTP)") (class "Default")
      (node (ref "SCL_S3_C3_C2") (pin "TP") (pinfunction "TP_TP") (pintype "input"))
    )
    (net (code "51") (name "unconnected-(SCL_S4_C1_C4-PadTP)") (class "Default")
      (node (ref "SCL_S4_C1_C4") (pin "TP") (pinfunction "TP_TP") (pintype "input"))
    )
    (net (code "52") (name "unconnected-(SCL_S4_C4-PadTP)") (class "Default")
      (node (ref "SCL_S4_C4") (pin "TP") (pinfunction "TP_TP") (pintype "input"))
    )
    (net (code "53") (name "unconnected-(SCL_S4_C4_C1-PadTP)") (class "Default")
      (node (ref "SCL_S4_C4_C1") (pin "TP") (pinfunction "TP_TP") (pintype "input"))
    )
    (net (code "54") (name "unconnected-(SCL_S4_C4_C2-PadTP)") (class "Default")
      (node (ref "SCL_S4_C4_C2") (pin "TP") (pinfunction "TP_TP") (pintype "input"))
    )
    (net (code "55") (name "unconnected-(SDA-PadTP)") (class "Default")
      (node (ref "SDA") (pin "TP") (pinfunction "TP_TP") (pintype "input"))
    )
    (net (code "56") (name "unconnected-(SDA2-PadTP)") (class "Default")
      (node (ref "SDA2") (pin "TP") (pinfunction "TP_TP") (pintype "input"))
    )
    (net (code "57") (name "unconnected-(SDA_S2_C1-PadTP)") (class "Default")
      (node (ref "SDA_S2_C1") (pin "TP") (pinfunction "TP_TP") (pintype "input"))
    )
    (net (code "58") (name "unconnected-(SDA_S2_C2_C2-PadTP)") (class "Default")
      (node (ref "SDA_S2_C2_C2") (pin "TP") (pinfunction "TP_TP") (pintype "input"))
    )
    (net (code "59") (name "unconnected-(SDA_S3_C1-PadTP)") (class "Default")
      (node (ref "SDA_S3_C1") (pin "TP") (pinfunction "TP_TP") (pintype "input"))
    )
    (net (code "60") (name "unconnected-(SDA_S3_C1_C1-PadTP)") (class "Default")
      (node (ref "SDA_S3_C1_C1") (pin "TP") (pinfunction "TP_TP") (pintype "input"))
    )
    (net (code "61") (name "unconnected-(SDA_S3_C3_C3-PadTP)") (class "Default")
      (node (ref "SDA_S3_C3_C3") (pin "TP") (pinfunction "TP_TP") (pintype "input"))
    )
    (net (code "62") (name "unconnected-(SDA_S3_C3_C4-PadTP)") (class "Default")
      (node (ref "SDA_S3_C3_C4") (pin "TP") (pinfunction "TP_TP") (pintype "input"))
    )
    (net (code "63") (name "unconnected-(SDA_S4_C1-PadTP)") (class "Default")
      (node (ref "SDA_S4_C1") (pin "TP") (pinfunction "TP_TP") (pintype "input"))
    )
    (net (code "64") (name "unconnected-(SDA_S4_C1_C1-PadTP)") (class "Default")
      (node (ref "SDA_S4_C1_C1") (pin "TP") (pinfunction "TP_TP") (pintype "input"))
    )
    (net (code "65") (name "unconnected-(SDA_S4_C4_C3-PadTP)") (class "Default")
      (node (ref "SDA_S4_C4_C3") (pin "TP") (pinfunction "TP_TP") (pintype "input"))
    )
    (net (code "66") (name "unconnected-(SDA_S4_C4_C4-PadTP)") (class "Default")
      (node (ref "SDA_S4_C4_C4") (pin "TP") (pinfunction "TP_TP") (pintype "input"))
    )
    (net (code "67") (name "unconnected-(VDDA_C1-PadTP)") (class "Default")
      (node (ref "VDDA_C1") (pin "TP") (pinfunction "TP_TP") (pintype "input"))
    )
    (net (code "68") (name "unconnected-(VDDA_C2-PadTP)") (class "Default")
      (node (ref "VDDA_C2") (pin "TP") (pinfunction "TP_TP") (pintype "input"))
    )
    (net (code "69") (name "unconnected-(VDDD_C1-PadTP)") (class "Default")
      (node (ref "VDDD_C1") (pin "TP") (pinfunction "TP_TP") (pintype "input"))
    )
    (net (code "70") (name "unconnected-(VDDD_C2-PadTP)") (class "Default")
      (node (ref "VDDD_C2") (pin "TP") (pinfunction "TP_TP") (pintype "input"))
    )
    (net (code "71") (name "unconnected-(VDDIO_C1-PadTP)") (class "Default")
      (node (ref "VDDIO_C1") (pin "TP") (pinfunction "TP_TP") (pintype "input"))
    )
    (net (code "72") (name "unconnected-(VDDIO_C2-PadTP)") (class "Default")
      (node (ref "VDDIO_C2") (pin "TP") (pinfunction "TP_TP") (pintype "input"))
    )
  )
)
